# REGENIX_DRIVER_3.net
KiCad netlist of a schematic drawn in Altium Designer
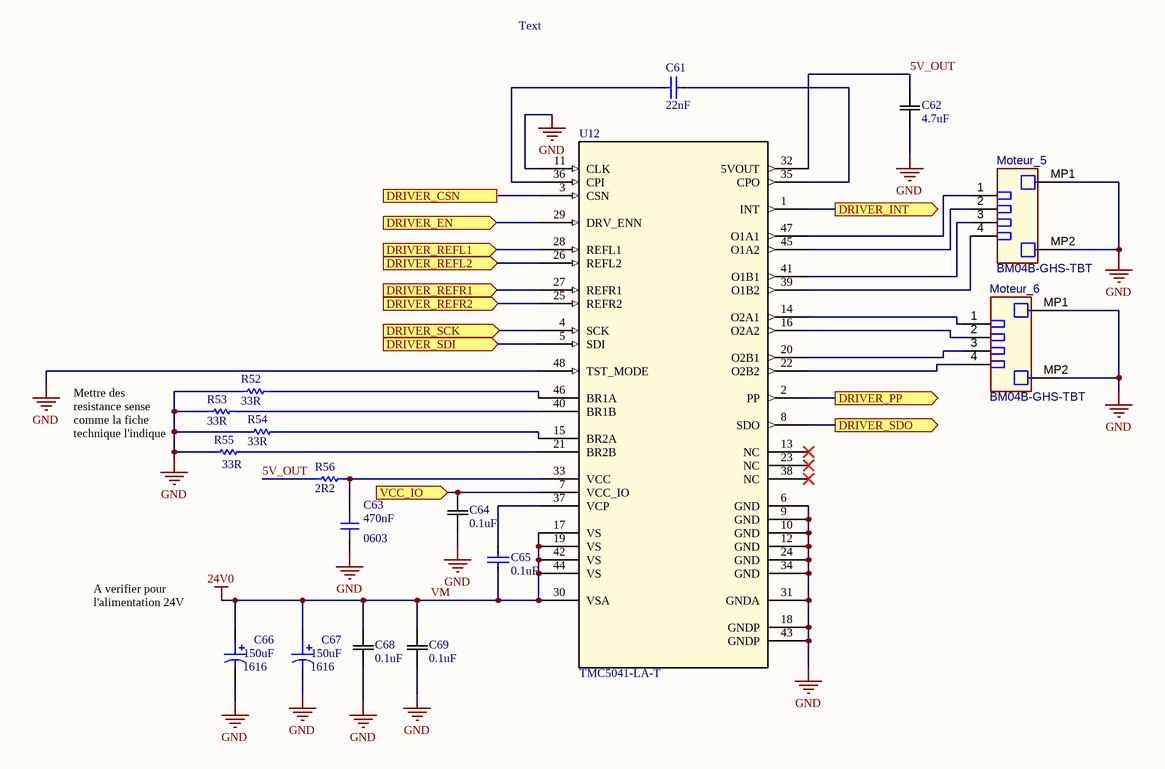
[diagram p0: REGENIX_DRIVER_3.SchDoc]

(export (version "E")
  (design (tool "Eeschema 10.0.6"))
  (components
    (comp (ref "C61")
      (value "22nF")
      (footprint "CAPACITOR-0603")
      (description "Capacitor-0603-0.22uF-25V-X7R")
      (libsource (lib "main_lib") (part "Capacitor-0603-0.22uF-25V-X7R"))
    )
    (comp (ref "C62")
      (value "4.7uF")
      (footprint "CAP_CL21_SAM")
      (description "CAP CER 4.7UF 25V X5R 0805  CL21A475KAQNNNE")
      (libsource (lib "CL21A475KAQNNNE") (part "CL21A475KAQNNNE"))
    )
    (comp (ref "C63")
      (value "470nF")
      (footprint "CAP_0603")
      (description "CAP - 0603")
      (fields (field (name "PACKAGE") "0603") (field (name "CREATEDBY") "Jonathan Bouchard"))
      (libsource (lib "S7CAS_LIB2023") (part "CAP - 0603"))
    )
    (comp (ref "C64")
      (value "0.1uF")
      (footprint "CAP_CL10_SAM")
      (description "CAP CER 0.1UF 50V X7R 0603 CL10B104KB8NNWC")
      (libsource (lib "CL10B104KB8NNWC") (part "CL10B104KB8NNWC"))
    )
    (comp (ref "C65")
      (value "0.1uF")
      (footprint "CAPACITOR-0603")
      (description "Capacitor-0603-0.22uF-25V-X7R")
      (libsource (lib "main_lib") (part "Capacitor-0603-0.22uF-25V-X7R"))
    )
    (comp (ref "C66")
      (value "150uF")
      (footprint "CAP_ALU_1616_vishay")
      (description "CAP - ALU 470uF 20% 50V - 1616")
      (fields
        (field (name "MFG") "Vishay Dale")
        (field (name "MFG PART NUMBER") "MAL214699108E3")
        (field (name "PACKAGE") "1616")
        (field (name "CREATEDBY") "Jonathan Bouchard")
      )
      (libsource (lib "S7CAS_LIB2023") (part "CAP_ALU_MAL214699108E3"))
    )
    (comp (ref "C67")
      (value "150uF")
      (footprint "CAP_ALU_1616_vishay")
      (description "CAP - ALU 470uF 20% 50V - 1616")
      (fields
        (field (name "MFG") "Vishay Dale")
        (field (name "MFG PART NUMBER") "MAL214699108E3")
        (field (name "PACKAGE") "1616")
        (field (name "CREATEDBY") "Jonathan Bouchard")
      )
      (libsource (lib "S7CAS_LIB2023") (part "CAP_ALU_MAL214699108E3"))
    )
    (comp (ref "C68")
      (value "0.1uF")
      (footprint "CAP_CL10_SAM")
      (description "CAP CER 0.1UF 50V X7R 0603 CL10B104KB8NNWC")
      (libsource (lib "CL10B104KB8NNWC") (part "CL10B104KB8NNWC"))
    )
    (comp (ref "C69")
      (value "0.1uF")
      (footprint "CAP_CL10_SAM")
      (description "CAP CER 0.1UF 50V X7R 0603 CL10B104KB8NNWC")
      (libsource (lib "CL10B104KB8NNWC") (part "CL10B104KB8NNWC"))
    )
    (comp (ref "Moteur_5")
      (value "BM04B-GHS-TBT")
      (footprint "JST-BM04B-GHS-TBT_V")
      (description "Header, Pitch 1.25 mm, 1 x 4 Position, Height 4.05 mm, -25 to 85 degC")
      (libsource (lib "Marylin Bechara") (part "CMP-00071-3"))
    )
    (comp (ref "Moteur_6")
      (value "BM04B-GHS-TBT")
      (footprint "JST-BM04B-GHS-TBT_V")
      (description "Header, Pitch 1.25 mm, 1 x 4 Position, Height 4.05 mm, -25 to 85 degC")
      (libsource (lib "Marylin Bechara") (part "CMP-00071-3"))
    )
    (comp (ref "R52")
      (value "33R")
      (footprint "RESISTOR-1206")
      (description "Resistor1206-33R")
      (fields (field (name "Comment") "SMT resistor"))
      (libsource (lib "main_lib") (part "Resistor1206-33R"))
    )
    (comp (ref "R53")
      (value "33R")
      (footprint "RESISTOR-1206")
      (description "Resistor1206-33R")
      (fields (field (name "Comment") "SMT resistor"))
      (libsource (lib "main_lib") (part "Resistor1206-33R"))
    )
    (comp (ref "R54")
      (value "33R")
      (footprint "RESISTOR-1206")
      (description "Resistor1206-33R")
      (fields (field (name "Comment") "SMT resistor"))
      (libsource (lib "main_lib") (part "Resistor1206-33R"))
    )
    (comp (ref "R55")
      (value "33R")
      (footprint "RESISTOR-1206")
      (description "Resistor1206-33R")
      (fields (field (name "Comment") "SMT resistor"))
      (libsource (lib "main_lib") (part "Resistor1206-33R"))
    )
    (comp (ref "R56")
      (value "2R2")
      (footprint "Resistor-0603")
      (description "Resistor0603-22R")
      (fields (field (name "Comment") "SMT resistor"))
      (libsource (lib "main_lib") (part "Resistor0603-22R"))
    )
    (comp (ref "U12")
      (value "TMC5041-LA-T")
      (footprint "QFN48_7X7_TRI")
      (description "No Description Available")
      (libsource (lib "TMC5041-LA-T") (part "TMC5041-LA-T"))
    )
  )
  (nets
    (net (code "1") (name "/5V_OUT") (class "Default")
      (node (ref "C62") (pin "2") (pinfunction "2_2") (pintype "passive"))
      (node (ref "R56") (pin "1") (pinfunction "1_1") (pintype "passive"))
      (node (ref "U12") (pin "32") (pinfunction "5VOUT_32") (pintype "output"))
    )
    (net (code "3") (name "/DRIVER_EN") (class "Default")
      (node (ref "U12") (pin "29") (pinfunction "DRV_ENN_29") (pintype "input"))
    )
    (net (code "4") (name "/DRIVER_INT") (class "Default")
      (node (ref "U12") (pin "1") (pinfunction "INT_1") (pintype "output"))
    )
    (net (code "5") (name "/DRIVER_PP") (class "Default")
      (node (ref "U12") (pin "2") (pinfunction "PP_2") (pintype "output"))
    )
    (net (code "6") (name "/DRIVER_REFL1") (class "Default")
      (node (ref "U12") (pin "28") (pinfunction "REFL1_28") (pintype "input"))
    )
    (net (code "7") (name "/DRIVER_REFL2") (class "Default")
      (node (ref "U12") (pin "26") (pinfunction "REFL2_26") (pintype "input"))
    )
    (net (code "8") (name "/DRIVER_REFR1") (class "Default")
      (node (ref "U12") (pin "27") (pinfunction "REFR1_27") (pintype "input"))
    )
    (net (code "9") (name "/DRIVER_REFR2") (class "Default")
      (node (ref "U12") (pin "25") (pinfunction "REFR2_25") (pintype "input"))
    )
    (net (code "10") (name "/DRIVER_SCK") (class "Default")
      (node (ref "U12") (pin "4") (pinfunction "SCK_4") (pintype "input"))
    )
    (net (code "11") (name "/DRIVER_SDI") (class "Default")
      (node (ref "U12") (pin "5") (pinfunction "SDI_5") (pintype "input"))
    )
    (net (code "12") (name "/DRIVER_SDO") (class "Default")
      (node (ref "U12") (pin "8") (pinfunction "SDO_8") (pintype "output"))
    )
    (net (code "13") (name "/VCC_IO") (class "Default")
      (node (ref "C64") (pin "2") (pinfunction "2_2") (pintype "passive"))
      (node (ref "U12") (pin "7") (pinfunction "VCC_IO_7") (pintype "power_in"))
    )
    (net (code "14") (name "24V0") (class "Default")
      (node (ref "C65") (pin "1") (pinfunction "1_1") (pintype "passive"))
      (node (ref "C66") (pin "1") (pinfunction "1_1") (pintype "passive"))
      (node (ref "C67") (pin "1") (pinfunction "1_1") (pintype "passive"))
      (node (ref "C68") (pin "2") (pinfunction "2_2") (pintype "passive"))
      (node (ref "C69") (pin "2") (pinfunction "2_2") (pintype "passive"))
      (node (ref "U12") (pin "17") (pinfunction "VS_17") (pintype "power_in"))
      (node (ref "U12") (pin "19") (pinfunction "VS_19") (pintype "power_in"))
      (node (ref "U12") (pin "30") (pinfunction "VSA_30") (pintype "power_in"))
      (node (ref "U12") (pin "42") (pinfunction "VS_42") (pintype "power_in"))
      (node (ref "U12") (pin "44") (pinfunction "VS_44") (pintype "power_in"))
    )
    (net (code "15") (name "GND") (class "Default")
      (node (ref "C62") (pin "1") (pinfunction "1_1") (pintype "passive"))
      (node (ref "C63") (pin "1") (pinfunction "1_1") (pintype "passive"))
      (node (ref "C64") (pin "1") (pinfunction "1_1") (pintype "passive"))
      (node (ref "C66") (pin "2") (pinfunction "2_2") (pintype "passive"))
      (node (ref "C67") (pin "2") (pinfunction "2_2") (pintype "passive"))
      (node (ref "C68") (pin "1") (pinfunction "1_1") (pintype "passive"))
      (node (ref "C69") (pin "1") (pinfunction "1_1") (pintype "passive"))
      (node (ref "Moteur_5") (pin "MP1") (pinfunction "MP1_MP1") (pintype "passive"))
      (node (ref "Moteur_5") (pin "MP2") (pinfunction "MP2_MP2") (pintype "passive"))
      (node (ref "Moteur_6") (pin "MP1") (pinfunction "MP1_MP1") (pintype "passive"))
      (node (ref "Moteur_6") (pin "MP2") (pinfunction "MP2_MP2") (pintype "passive"))
      (node (ref "R52") (pin "1") (pinfunction "1_1") (pintype "passive"))
      (node (ref "R53") (pin "1") (pinfunction "1_1") (pintype "passive"))
      (node (ref "R54") (pin "1") (pinfunction "1_1") (pintype "passive"))
      (node (ref "R55") (pin "1") (pinfunction "1_1") (pintype "passive"))
      (node (ref "U12") (pin "10") (pinfunction "GND_10") (pintype "power_in"))
      (node (ref "U12") (pin "11") (pinfunction "CLK_11") (pintype "input"))
      (node (ref "U12") (pin "12") (pinfunction "GND_12") (pintype "power_in"))
      (node (ref "U12") (pin "18") (pinfunction "GNDP_18") (pintype "power_in"))
      (node (ref "U12") (pin "24") (pinfunction "GND_24") (pintype "power_in"))
      (node (ref "U12") (pin "31") (pinfunction "GNDA_31") (pintype "power_in"))
      (node (ref "U12") (pin "34") (pinfunction "GND_34") (pintype "power_in"))
      (node (ref "U12") (pin "43") (pinfunction "GNDP_43") (pintype "power_in"))
      (node (ref "U12") (pin "48") (pinfunction "TST_MODE_48") (pintype "input"))
      (node (ref "U12") (pin "6") (pinfunction "GND_6") (pintype "power_in"))
      (node (ref "U12") (pin "9") (pinfunction "GND_9") (pintype "power_in"))
    )
    (net (code "16") (name "Net-(U12-BR1A)") (class "Default")
      (node (ref "R52") (pin "2") (pinfunction "2_2") (pintype "passive"))
      (node (ref "U12") (pin "46") (pinfunction "BR1A_46") (pintype "passive"))
    )
    (net (code "17") (name "Net-(U12-BR1B)") (class "Default")
      (node (ref "R53") (pin "2") (pinfunction "2_2") (pintype "passive"))
      (node (ref "U12") (pin "40") (pinfunction "BR1B_40") (pintype "passive"))
    )
    (net (code "18") (name "Net-(U12-BR2A)") (class "Default")
      (node (ref "R54") (pin "2") (pinfunction "2_2") (pintype "passive"))
      (node (ref "U12") (pin "15") (pinfunction "BR2A_15") (pintype "passive"))
    )
    (net (code "19") (name "Net-(U12-BR2B)") (class "Default")
      (node (ref "R55") (pin "2") (pinfunction "2_2") (pintype "passive"))
      (node (ref "U12") (pin "21") (pinfunction "BR2B_21") (pintype "passive"))
    )
    (net (code "20") (name "Net-(U12-CPI)") (class "Default")
      (node (ref "C61") (pin "1") (pinfunction "1_1") (pintype "passive"))
      (node (ref "U12") (pin "36") (pinfunction "CPI_36") (pintype "input"))
    )
    (net (code "21") (name "Net-(U12-CPO)") (class "Default")
      (node (ref "C61") (pin "2") (pinfunction "2_2") (pintype "passive"))
      (node (ref "U12") (pin "35") (pinfunction "CPO_35") (pintype "output"))
    )
    (net (code "22") (name "Net-(U12-O1A1)") (class "Default")
      (node (ref "Moteur_5") (pin "1") (pinfunction "1_1") (pintype "passive"))
      (node (ref "U12") (pin "47") (pinfunction "O1A1_47") (pintype "output"))
    )
    (net (code "23") (name "Net-(U12-O1A2)") (class "Default")
      (node (ref "Moteur_5") (pin "2") (pinfunction "2_2") (pintype "passive"))
      (node (ref "U12") (pin "45") (pinfunction "O1A2_45") (pintype "output"))
    )
    (net (code "24") (name "Net-(U12-O1B1)") (class "Default")
      (node (ref "Moteur_5") (pin "3") (pinfunction "3_3") (pintype "passive"))
      (node (ref "U12") (pin "41") (pinfunction "O1B1_41") (pintype "output"))
    )
    (net (code "25") (name "Net-(U12-O1B2)") (class "Default")
      (node (ref "Moteur_5") (pin "4") (pinfunction "4_4") (pintype "passive"))
      (node (ref "U12") (pin "39") (pinfunction "O1B2_39") (pintype "output"))
    )
    (net (code "26") (name "Net-(U12-O2A1)") (class "Default")
      (node (ref "Moteur_6") (pin "1") (pinfunction "1_1") (pintype "passive"))
      (node (ref "U12") (pin "14") (pinfunction "O2A1_14") (pintype "output"))
    )
    (net (code "27") (name "Net-(U12-O2A2)") (class "Default")
      (node (ref "Moteur_6") (pin "2") (pinfunction "2_2") (pintype "passive"))
      (node (ref "U12") (pin "16") (pinfunction "O2A2_16") (pintype "output"))
    )
    (net (code "28") (name "Net-(U12-O2B1)") (class "Default")
      (node (ref "Moteur_6") (pin "3") (pinfunction "3_3") (pintype "passive"))
      (node (ref "U12") (pin "20") (pinfunction "O2B1_20") (pintype "output"))
    )
    (net (code "29") (name "Net-(U12-O2B2)") (class "Default")
      (node (ref "Moteur_6") (pin "4") (pinfunction "4_4") (pintype "passive"))
      (node (ref "U12") (pin "22") (pinfunction "O2B2_22") (pintype "output"))
    )
    (net (code "30") (name "Net-(U12-VCC)") (class "Default")
      (node (ref "C63") (pin "2") (pinfunction "2_2") (pintype "passive"))
      (node (ref "R56") (pin "2") (pinfunction "2_2") (pintype "passive"))
      (node (ref "U12") (pin "33") (pinfunction "VCC_33") (pintype "power_in"))
    )
    (net (code "31") (name "Net-(U12-VCP)") (class "Default")
      (node (ref "C65") (pin "2") (pinfunction "2_2") (pintype "passive"))
      (node (ref "U12") (pin "37") (pinfunction "VCP_37") (pintype "power_in"))
    )
    (net (code "32") (name "unconnected-(U12-CSN-Pad3)") (class "Default")
      (node (ref "U12") (pin "3") (pinfunction "CSN_3") (pintype "input"))
    )
    (net (code "33") (name "unconnected-(U12-NC-Pad13)") (class "Default")
      (node (ref "U12") (pin "13") (pinfunction "NC_13") (pintype "passive+no_connect"))
    )
    (net (code "34") (name "unconnected-(U12-NC-Pad23)") (class "Default")
      (node (ref "U12") (pin "23") (pinfunction "NC_23") (pintype "passive+no_connect"))
    )
    (net (code "35") (name "unconnected-(U12-NC-Pad38)") (class "Default")
      (node (ref "U12") (pin "38") (pinfunction "NC_38") (pintype "passive+no_connect"))
    )
  )
)
